# main.net
KiCad netlist of a schematic drawn in EAGLE
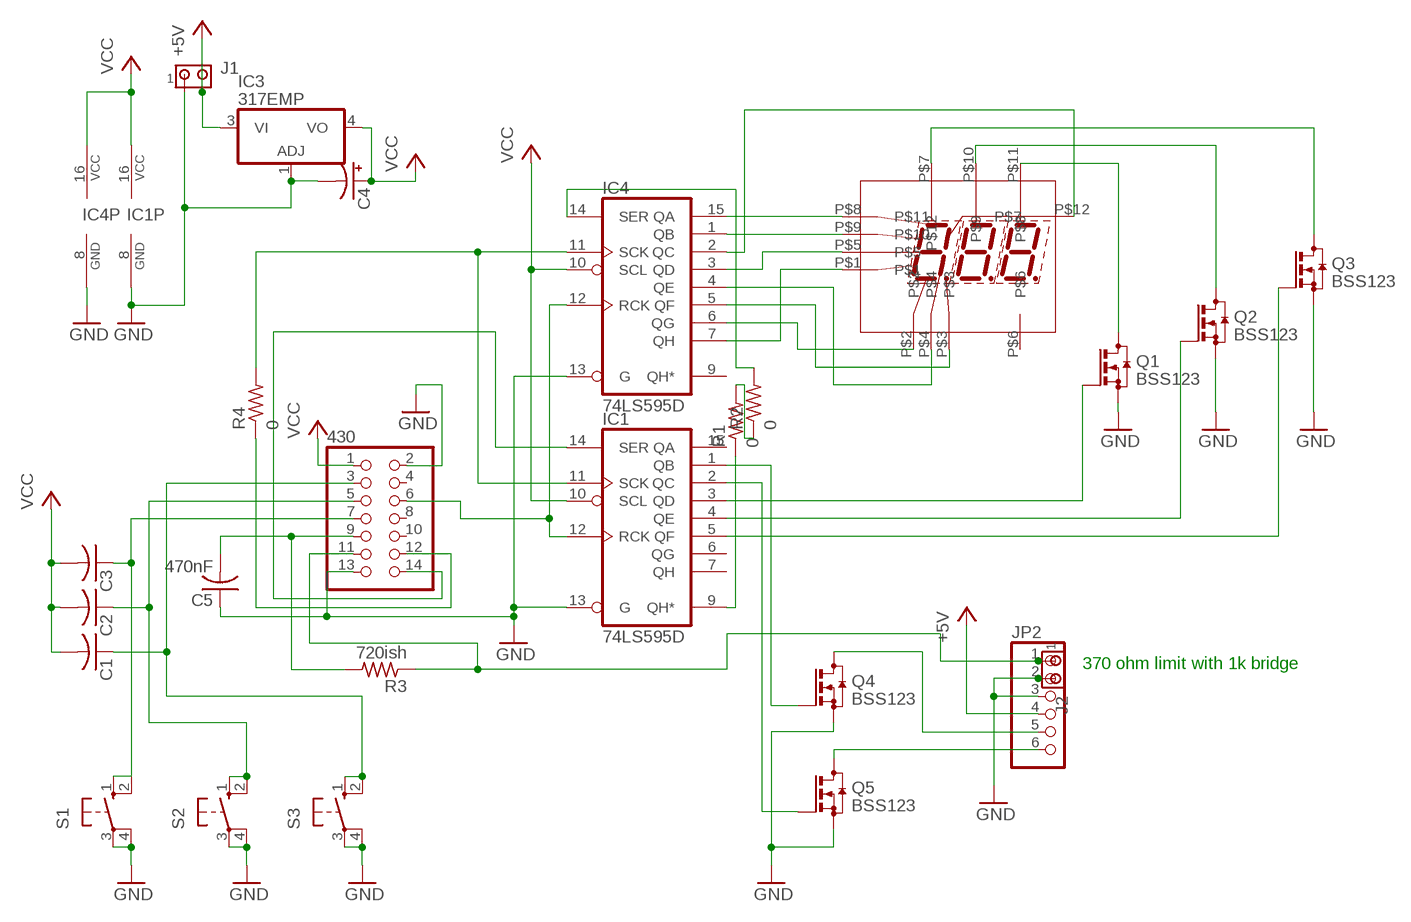
[diagram p0: schematic, sheet 1]

(export (version "E")
  (design (tool "Eeschema 10.0.6"))
  (components
    (comp (ref "430")
      (value "PINHD-2X7")
      (footprint "eagle-import:2X07")
      (libsource (lib "eagle-import") (part "PINHD-2X7"))
    )
    (comp (ref "C1")
      (value "C-USC0603K")
      (footprint "eagle-import:C0603K")
      (libsource (lib "eagle-import") (part "C-USC0603K"))
    )
    (comp (ref "C2")
      (value "C-USC0603K")
      (footprint "eagle-import:C0603K")
      (libsource (lib "eagle-import") (part "C-USC0603K"))
    )
    (comp (ref "C3")
      (value "C-USC0603K")
      (footprint "eagle-import:C0603K")
      (libsource (lib "eagle-import") (part "C-USC0603K"))
    )
    (comp (ref "C4")
      (value "CPOL-USE2.5-7")
      (footprint "eagle-import:E2,5-7")
      (libsource (lib "eagle-import") (part "CPOL-USE2.5-7"))
    )
    (comp (ref "C5")
      (value "470nF")
      (footprint "eagle-import:C0603K")
      (libsource (lib "eagle-import") (part "C-USC0603K"))
    )
    (comp (ref "IC1")
      (value "74LS595D")
      (footprint "eagle-import:SO16")
      (libsource (lib "eagle-import") (part "74595DLS"))
    )
    (comp (ref "IC3")
      (value "317EMP")
      (footprint "eagle-import:SOT223")
      (libsource (lib "eagle-import") (part "317EMP"))
    )
    (comp (ref "IC4")
      (value "74LS595D")
      (footprint "eagle-import:SO16")
      (libsource (lib "eagle-import") (part "74595DLS"))
    )
    (comp (ref "J1")
      (value "MTA02-100")
      (footprint "eagle-import:10X02MTA")
      (libsource (lib "eagle-import") (part "MTA02-100"))
    )
    (comp (ref "J2")
      (value "MTA02-100")
      (footprint "eagle-import:10X02MTA")
      (libsource (lib "eagle-import") (part "MTA02-100"))
    )
    (comp (ref "JP2")
      (value "PINHD-1X6")
      (footprint "eagle-import:1X06")
      (libsource (lib "eagle-import") (part "PINHD-1X6"))
    )
    (comp (ref "Q1")
      (value "BSS123")
      (footprint "eagle-import:SOT23")
      (libsource (lib "eagle-import") (part "BSS123"))
    )
    (comp (ref "Q2")
      (value "BSS123")
      (footprint "eagle-import:SOT23")
      (libsource (lib "eagle-import") (part "BSS123"))
    )
    (comp (ref "Q3")
      (value "BSS123")
      (footprint "eagle-import:SOT23")
      (libsource (lib "eagle-import") (part "BSS123"))
    )
    (comp (ref "Q4")
      (value "BSS123")
      (footprint "eagle-import:SOT23")
      (libsource (lib "eagle-import") (part "BSS123"))
    )
    (comp (ref "Q5")
      (value "BSS123")
      (footprint "eagle-import:SOT23")
      (libsource (lib "eagle-import") (part "BSS123"))
    )
    (comp (ref "R1")
      (value "0")
      (footprint "eagle-import:R0603")
      (libsource (lib "eagle-import") (part "R-US_R0603"))
    )
    (comp (ref "R2")
      (value "0")
      (footprint "eagle-import:R0603")
      (libsource (lib "eagle-import") (part "R-US_R0603"))
    )
    (comp (ref "R3")
      (value "720ish")
      (footprint "eagle-import:R0805")
      (libsource (lib "eagle-import") (part "R-US_R0805"))
    )
    (comp (ref "R4")
      (value "0")
      (footprint "eagle-import:R0603")
      (libsource (lib "eagle-import") (part "R-US_R0603"))
    )
    (comp (ref "S1")
      (value "10-XX")
      (footprint "eagle-import:B3F-10XX")
      (fields (field (name "MPN") "B3F-1000"))
      (libsource (lib "eagle-import") (part "10-XX"))
    )
    (comp (ref "S2")
      (value "10-XX")
      (footprint "eagle-import:B3F-10XX")
      (fields (field (name "MPN") "B3F-1000"))
      (libsource (lib "eagle-import") (part "10-XX"))
    )
    (comp (ref "S3")
      (value "10-XX")
      (footprint "eagle-import:B3F-10XX")
      (fields (field (name "MPN") "B3F-1000"))
      (libsource (lib "eagle-import") (part "10-XX"))
    )
    (comp (ref "U$1")
      (value "BL-T52C-31")
      (footprint "eagle-import:BL-T52X-31")
      (libsource (lib "eagle-import") (part "BL-T52C-31"))
    )
  )
  (nets
    (net (code "1") (name "+5V") (class "Default")
      (node (ref "IC3") (pin "3") (pinfunction "VI_3") (pintype "input"))
      (node (ref "J1") (pin "2") (pinfunction "2_2") (pintype "passive"))
      (node (ref "JP2") (pin "4") (pinfunction "4_4") (pintype "passive"))
    )
    (net (code "2") (name "GND") (class "Default")
      (node (ref "430") (pin "13") (pinfunction "13_13") (pintype "passive"))
      (node (ref "430") (pin "2") (pinfunction "2_2") (pintype "passive"))
      (node (ref "C4") (pin "-") (pinfunction "-_-") (pintype "passive"))
      (node (ref "C5") (pin "1") (pinfunction "1_1") (pintype "passive"))
      (node (ref "IC1") (pin "13") (pinfunction "G_13") (pintype "input"))
      (node (ref "IC1") (pin "8") (pinfunction "GND_8") (pintype "power_in"))
      (node (ref "IC3") (pin "1") (pinfunction "ADJ_1") (pintype "input"))
      (node (ref "IC4") (pin "13") (pinfunction "G_13") (pintype "input"))
      (node (ref "IC4") (pin "8") (pinfunction "GND_8") (pintype "power_in"))
      (node (ref "J1") (pin "1") (pinfunction "1_1") (pintype "passive"))
      (node (ref "J2") (pin "2") (pinfunction "2_2") (pintype "passive"))
      (node (ref "JP2") (pin "2") (pinfunction "2_2") (pintype "passive"))
      (node (ref "JP2") (pin "3") (pinfunction "3_3") (pintype "passive"))
      (node (ref "Q1") (pin "2") (pinfunction "S_2") (pintype "passive"))
      (node (ref "Q2") (pin "2") (pinfunction "S_2") (pintype "passive"))
      (node (ref "Q3") (pin "2") (pinfunction "S_2") (pintype "passive"))
      (node (ref "Q4") (pin "2") (pinfunction "S_2") (pintype "passive"))
      (node (ref "Q5") (pin "2") (pinfunction "S_2") (pintype "passive"))
      (node (ref "S1") (pin "3") (pinfunction "P_3") (pintype "passive"))
      (node (ref "S1") (pin "4") (pinfunction "P1_4") (pintype "passive"))
      (node (ref "S2") (pin "3") (pinfunction "P_3") (pintype "passive"))
      (node (ref "S2") (pin "4") (pinfunction "P1_4") (pintype "passive"))
      (node (ref "S3") (pin "3") (pinfunction "P_3") (pintype "passive"))
      (node (ref "S3") (pin "4") (pinfunction "P1_4") (pintype "passive"))
    )
    (net (code "3") (name "Net-(430-Pad9)") (class "Default")
      (node (ref "430") (pin "9") (pinfunction "9_9") (pintype "passive"))
      (node (ref "C5") (pin "2") (pinfunction "2_2") (pintype "passive"))
      (node (ref "R3") (pin "2") (pinfunction "2_2") (pintype "passive"))
    )
    (net (code "4") (name "Net-(430-Pad11)") (class "Default")
      (node (ref "430") (pin "11") (pinfunction "11_11") (pintype "passive"))
      (node (ref "J2") (pin "1") (pinfunction "1_1") (pintype "passive"))
      (node (ref "JP2") (pin "1") (pinfunction "1_1") (pintype "passive"))
      (node (ref "R3") (pin "1") (pinfunction "1_1") (pintype "passive"))
    )
    (net (code "5") (name "Net-(430-Pad12)") (class "Default")
      (node (ref "430") (pin "12") (pinfunction "12_12") (pintype "passive"))
      (node (ref "R4") (pin "1") (pinfunction "1_1") (pintype "passive"))
    )
    (net (code "6") (name "Net-(IC1A-QB)") (class "Default")
      (node (ref "IC1") (pin "1") (pinfunction "QB_1") (pintype "tri_state"))
      (node (ref "Q4") (pin "1") (pinfunction "G_1") (pintype "passive"))
    )
    (net (code "7") (name "Net-(IC1A-QC)") (class "Default")
      (node (ref "IC1") (pin "2") (pinfunction "QC_2") (pintype "tri_state"))
      (node (ref "Q5") (pin "1") (pinfunction "G_1") (pintype "passive"))
    )
    (net (code "8") (name "Net-(IC1A-QD)") (class "Default")
      (node (ref "IC1") (pin "3") (pinfunction "QD_3") (pintype "tri_state"))
      (node (ref "Q1") (pin "1") (pinfunction "G_1") (pintype "passive"))
    )
    (net (code "9") (name "Net-(IC1A-QE)") (class "Default")
      (node (ref "IC1") (pin "4") (pinfunction "QE_4") (pintype "tri_state"))
      (node (ref "Q2") (pin "1") (pinfunction "G_1") (pintype "passive"))
    )
    (net (code "10") (name "Net-(IC1A-QF)") (class "Default")
      (node (ref "IC1") (pin "5") (pinfunction "QF_5") (pintype "tri_state"))
      (node (ref "Q3") (pin "1") (pinfunction "G_1") (pintype "passive"))
    )
    (net (code "11") (name "Net-(IC1A-QH*)") (class "Default")
      (node (ref "IC1") (pin "9") (pinfunction "QH*_9") (pintype "tri_state"))
      (node (ref "R1") (pin "1") (pinfunction "1_1") (pintype "passive"))
    )
    (net (code "12") (name "Net-(IC1A-RCK)") (class "Default")
      (node (ref "430") (pin "6") (pinfunction "6_6") (pintype "passive"))
      (node (ref "IC1") (pin "12") (pinfunction "RCK_12") (pintype "input"))
      (node (ref "IC4") (pin "12") (pinfunction "RCK_12") (pintype "input"))
    )
    (net (code "13") (name "Net-(IC1A-SCK)") (class "Default")
      (node (ref "IC1") (pin "11") (pinfunction "SCK_11") (pintype "input"))
      (node (ref "IC4") (pin "11") (pinfunction "SCK_11") (pintype "input"))
      (node (ref "R4") (pin "2") (pinfunction "2_2") (pintype "passive"))
    )
    (net (code "14") (name "Net-(IC1A-SER)") (class "Default")
      (node (ref "430") (pin "14") (pinfunction "14_14") (pintype "passive"))
      (node (ref "IC1") (pin "14") (pinfunction "SER_14") (pintype "input"))
    )
    (net (code "15") (name "Net-(IC4A-QA)") (class "Default")
      (node (ref "IC4") (pin "15") (pinfunction "QA_15") (pintype "tri_state"))
      (node (ref "U$1") (pin "P$8") (pinfunction "P$11_P$8") (pintype "bidirectional"))
    )
    (net (code "16") (name "Net-(IC4A-QB)") (class "Default")
      (node (ref "IC4") (pin "1") (pinfunction "QB_1") (pintype "tri_state"))
      (node (ref "U$1") (pin "P$9") (pinfunction "P$10_P$9") (pintype "bidirectional"))
    )
    (net (code "17") (name "Net-(IC4A-QC)") (class "Default")
      (node (ref "IC4") (pin "2") (pinfunction "QC_2") (pintype "tri_state"))
      (node (ref "U$1") (pin "P$12") (pinfunction "P$7_P$12") (pintype "bidirectional"))
    )
    (net (code "18") (name "Net-(IC4A-QD)") (class "Default")
      (node (ref "IC4") (pin "3") (pinfunction "QD_3") (pintype "tri_state"))
      (node (ref "U$1") (pin "P$5") (pinfunction "P$5_P$5") (pintype "bidirectional"))
    )
    (net (code "19") (name "Net-(IC4A-QE)") (class "Default")
      (node (ref "IC4") (pin "4") (pinfunction "QE_4") (pintype "tri_state"))
      (node (ref "U$1") (pin "P$4") (pinfunction "P$4_P$4") (pintype "bidirectional"))
    )
    (net (code "20") (name "Net-(IC4A-QF)") (class "Default")
      (node (ref "IC4") (pin "5") (pinfunction "QF_5") (pintype "tri_state"))
      (node (ref "U$1") (pin "P$3") (pinfunction "P$3_P$3") (pintype "bidirectional"))
    )
    (net (code "21") (name "Net-(IC4A-QG)") (class "Default")
      (node (ref "IC4") (pin "6") (pinfunction "QG_6") (pintype "tri_state"))
      (node (ref "U$1") (pin "P$2") (pinfunction "P$2_P$2") (pintype "bidirectional"))
    )
    (net (code "22") (name "Net-(IC4A-QH)") (class "Default")
      (node (ref "IC4") (pin "7") (pinfunction "QH_7") (pintype "tri_state"))
      (node (ref "U$1") (pin "P$1") (pinfunction "P$1_P$1") (pintype "bidirectional"))
    )
    (net (code "23") (name "Net-(IC4A-SER)") (class "Default")
      (node (ref "IC4") (pin "14") (pinfunction "SER_14") (pintype "input"))
      (node (ref "R2") (pin "2") (pinfunction "2_2") (pintype "passive"))
    )
    (net (code "24") (name "Net-(Q1-D)") (class "Default")
      (node (ref "Q1") (pin "3") (pinfunction "D_3") (pintype "passive"))
      (node (ref "U$1") (pin "P$11") (pinfunction "P$8_P$11") (pintype "bidirectional"))
    )
    (net (code "25") (name "Net-(Q2-D)") (class "Default")
      (node (ref "Q2") (pin "3") (pinfunction "D_3") (pintype "passive"))
      (node (ref "U$1") (pin "P$10") (pinfunction "P$9_P$10") (pintype "bidirectional"))
    )
    (net (code "26") (name "Net-(Q3-D)") (class "Default")
      (node (ref "Q3") (pin "3") (pinfunction "D_3") (pintype "passive"))
      (node (ref "U$1") (pin "P$7") (pinfunction "P$12_P$7") (pintype "bidirectional"))
    )
    (net (code "27") (name "Net-(Q4-D)") (class "Default")
      (node (ref "JP2") (pin "5") (pinfunction "5_5") (pintype "passive"))
      (node (ref "Q4") (pin "3") (pinfunction "D_3") (pintype "passive"))
    )
    (net (code "28") (name "Net-(Q5-D)") (class "Default")
      (node (ref "JP2") (pin "6") (pinfunction "6_6") (pintype "passive"))
      (node (ref "Q5") (pin "3") (pinfunction "D_3") (pintype "passive"))
    )
    (net (code "29") (name "Net-(R1-Pad2)") (class "Default")
      (node (ref "R1") (pin "2") (pinfunction "2_2") (pintype "passive"))
      (node (ref "R2") (pin "1") (pinfunction "1_1") (pintype "passive"))
    )
    (net (code "30") (name "Net-(S1-S)") (class "Default")
      (node (ref "430") (pin "7") (pinfunction "7_7") (pintype "passive"))
      (node (ref "C3") (pin "1") (pinfunction "1_1") (pintype "passive"))
      (node (ref "S1") (pin "1") (pinfunction "S_1") (pintype "passive"))
      (node (ref "S1") (pin "2") (pinfunction "S1_2") (pintype "passive"))
    )
    (net (code "31") (name "Net-(S2-S)") (class "Default")
      (node (ref "430") (pin "5") (pinfunction "5_5") (pintype "passive"))
      (node (ref "C2") (pin "1") (pinfunction "1_1") (pintype "passive"))
      (node (ref "S2") (pin "1") (pinfunction "S_1") (pintype "passive"))
      (node (ref "S2") (pin "2") (pinfunction "S1_2") (pintype "passive"))
    )
    (net (code "32") (name "Net-(S3-S)") (class "Default")
      (node (ref "430") (pin "3") (pinfunction "3_3") (pintype "passive"))
      (node (ref "C1") (pin "1") (pinfunction "1_1") (pintype "passive"))
      (node (ref "S3") (pin "1") (pinfunction "S_1") (pintype "passive"))
      (node (ref "S3") (pin "2") (pinfunction "S1_2") (pintype "passive"))
    )
    (net (code "33") (name "VCC") (class "Default")
      (node (ref "430") (pin "1") (pinfunction "1_1") (pintype "passive"))
      (node (ref "C1") (pin "2") (pinfunction "2_2") (pintype "passive"))
      (node (ref "C2") (pin "2") (pinfunction "2_2") (pintype "passive"))
      (node (ref "C3") (pin "2") (pinfunction "2_2") (pintype "passive"))
      (node (ref "C4") (pin "+") (pinfunction "+_+") (pintype "passive"))
      (node (ref "IC1") (pin "10") (pinfunction "SCL_10") (pintype "input"))
      (node (ref "IC1") (pin "16") (pinfunction "VCC_16") (pintype "power_in"))
      (node (ref "IC3") (pin "4") (pinfunction "VO_4") (pintype "passive"))
      (node (ref "IC4") (pin "10") (pinfunction "SCL_10") (pintype "input"))
      (node (ref "IC4") (pin "16") (pinfunction "VCC_16") (pintype "power_in"))
    )
    (net (code "34") (name "unconnected-(430-Pad4)") (class "Default")
      (node (ref "430") (pin "4") (pinfunction "4_4") (pintype "passive"))
    )
    (net (code "35") (name "unconnected-(430-Pad8)") (class "Default")
      (node (ref "430") (pin "8") (pinfunction "8_8") (pintype "passive"))
    )
    (net (code "36") (name "unconnected-(430-Pad10)") (class "Default")
      (node (ref "430") (pin "10") (pinfunction "10_10") (pintype "passive"))
    )
    (net (code "37") (name "unconnected-(IC1A-QA-Pad15)") (class "Default")
      (node (ref "IC1") (pin "15") (pinfunction "QA_15") (pintype "tri_state"))
    )
    (net (code "38") (name "unconnected-(IC1A-QG-Pad6)") (class "Default")
      (node (ref "IC1") (pin "6") (pinfunction "QG_6") (pintype "tri_state"))
    )
    (net (code "39") (name "unconnected-(IC1A-QH-Pad7)") (class "Default")
      (node (ref "IC1") (pin "7") (pinfunction "QH_7") (pintype "tri_state"))
    )
    (net (code "40") (name "unconnected-(IC4A-QH*-Pad9)") (class "Default")
      (node (ref "IC4") (pin "9") (pinfunction "QH*_9") (pintype "tri_state"))
    )
    (net (code "41") (name "unconnected-(U$1-PadP$6)") (class "Default")
      (node (ref "U$1") (pin "P$6") (pinfunction "P$6_P$6") (pintype "bidirectional"))
    )
  )
)
